# CRSpill.net
KiCad netlist of a schematic drawn in EAGLE
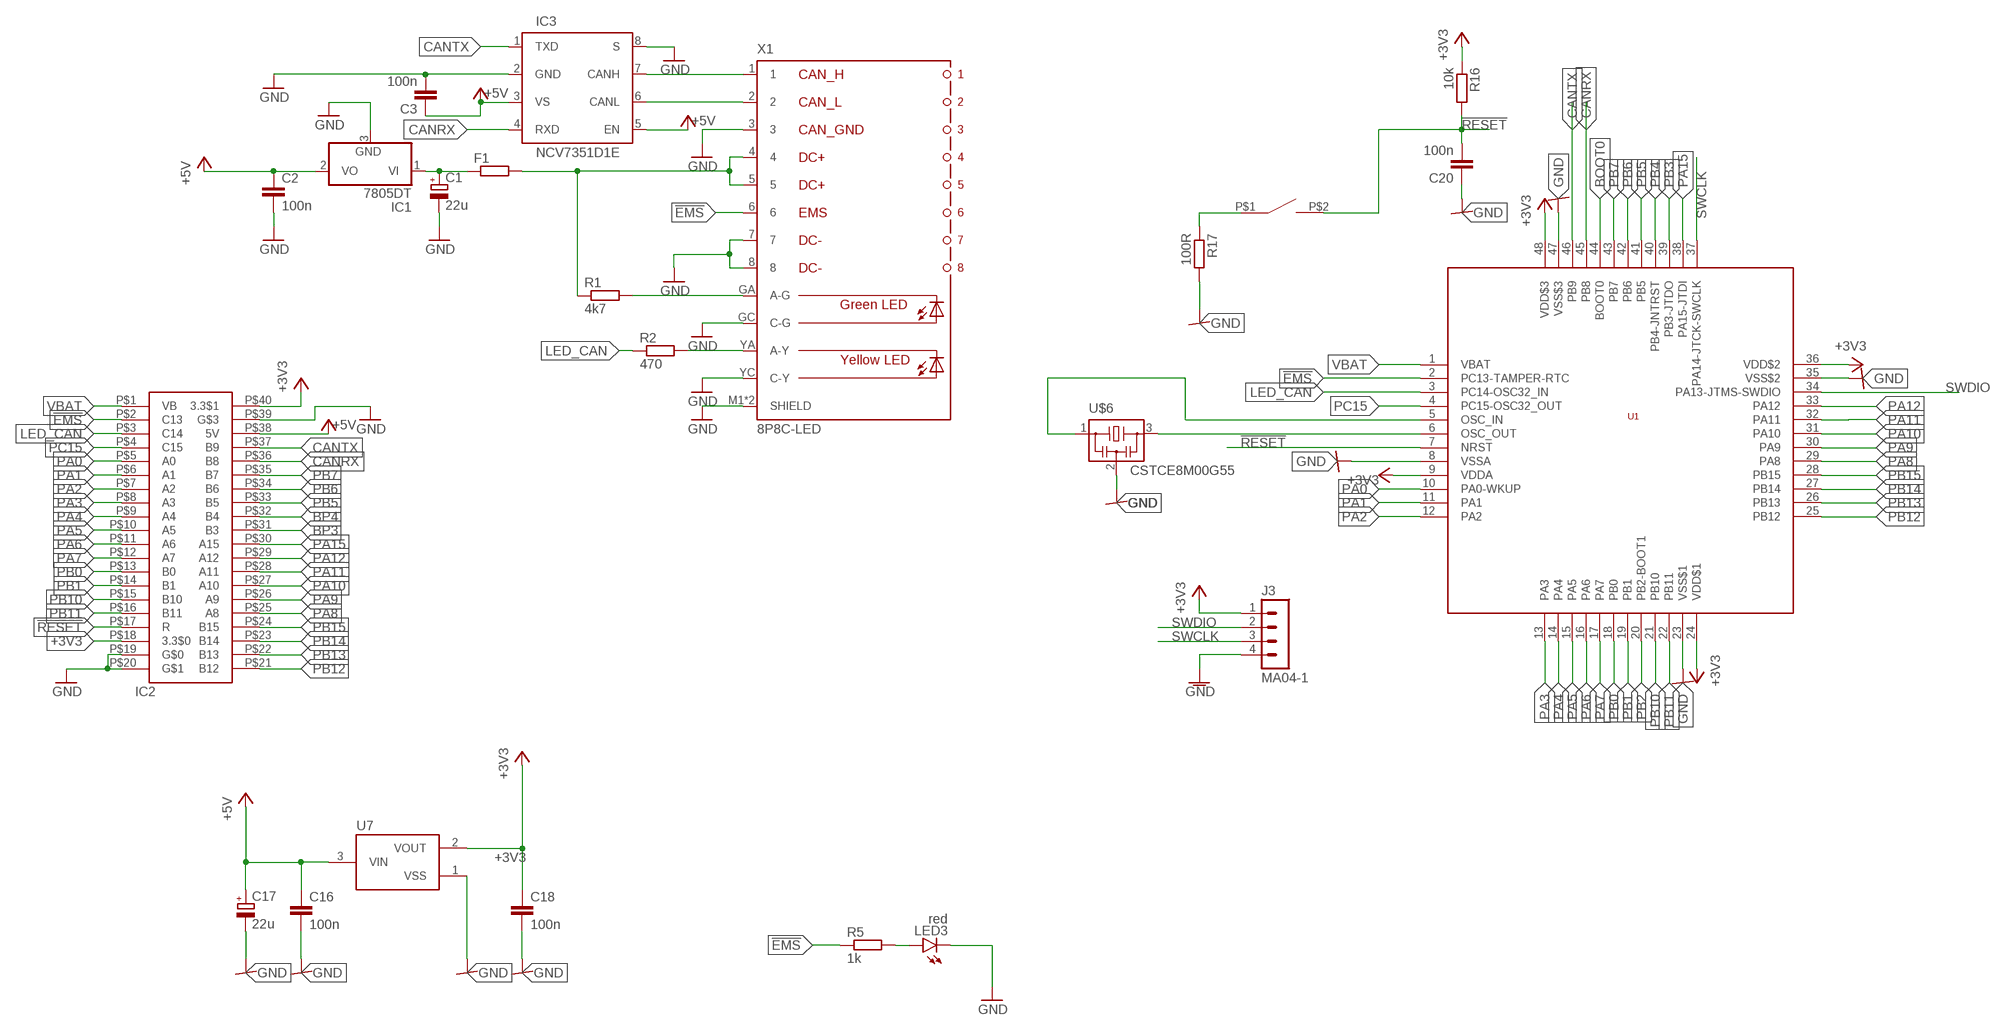
[diagram p0: schematic, sheet 1]

(export (version "E")
  (design (tool "Eeschema 10.0.6"))
  (components
    (comp (ref "C1")
      (value "22u")
      (footprint "eagle-import:E2,5-5")
      (libsource (lib "eagle-import") (part "rcl_334_CPOL-EUE2.5-5"))
    )
    (comp (ref "C2")
      (value "100n")
      (footprint "eagle-import:C0603")
      (libsource (lib "eagle-import") (part "rcl_334_C-EUC0603"))
    )
    (comp (ref "C3")
      (value "100n")
      (footprint "eagle-import:C0603")
      (libsource (lib "eagle-import") (part "rcl_334_C-EUC0603"))
    )
    (comp (ref "C16")
      (value "100n")
      (footprint "eagle-import:C0603")
      (libsource (lib "eagle-import") (part "C-EUC0603"))
    )
    (comp (ref "C17")
      (value "22u")
      (footprint "eagle-import:E2-5")
      (libsource (lib "eagle-import") (part "CPOL-EUE2-5"))
    )
    (comp (ref "C18")
      (value "100n")
      (footprint "eagle-import:C0603")
      (libsource (lib "eagle-import") (part "C-EUC0603"))
    )
    (comp (ref "C20")
      (value "100n")
      (footprint "eagle-import:C0603")
      (libsource (lib "eagle-import") (part "C-EUC0603"))
    )
    (comp (ref "F1")
      (value "R-EU_R1206")
      (footprint "eagle-import:R1206")
      (libsource (lib "eagle-import") (part "rcl_334_R-EU_R1206"))
    )
    (comp (ref "IC1")
      (value "7805DT")
      (footprint "eagle-import:TO252")
      (libsource (lib "eagle-import") (part "78DT05"))
    )
    (comp (ref "IC2")
      (value "BLUE_PILL")
      (footprint "eagle-import:BLUE_PILL")
      (libsource (lib "eagle-import") (part "BLUE_PILL"))
    )
    (comp (ref "IC3")
      (value "NCV7351D1E")
      (footprint "eagle-import:SO08")
      (libsource (lib "eagle-import") (part "NCV7351D1E"))
    )
    (comp (ref "J3")
      (value "MA04-1")
      (footprint "eagle-import:MA04-1")
      (libsource (lib "eagle-import") (part "MA04-1"))
    )
    (comp (ref "LED3")
      (value "red")
      (footprint "eagle-import:CHIPLED_0805")
      (libsource (lib "eagle-import") (part "LEDCHIPLED_0805"))
    )
    (comp (ref "R1")
      (value "4k7")
      (footprint "eagle-import:R0603")
      (libsource (lib "eagle-import") (part "rcl_334_R-EU_R0603"))
    )
    (comp (ref "R2")
      (value "470")
      (footprint "eagle-import:R0603")
      (libsource (lib "eagle-import") (part "rcl_334_R-EU_R0603"))
    )
    (comp (ref "R5")
      (value "1k")
      (footprint "eagle-import:R0603")
      (libsource (lib "eagle-import") (part "rcl_334_R-EU_R0603"))
    )
    (comp (ref "R16")
      (value "10k")
      (footprint "eagle-import:R0603")
      (libsource (lib "eagle-import") (part "R-EU_R0603"))
    )
    (comp (ref "R17")
      (value "100R")
      (footprint "eagle-import:R0603")
      (libsource (lib "eagle-import") (part "R-EU_R0603"))
    )
    (comp (ref "SW1")
      (value "SWITCH_TACTILETOP")
      (footprint "eagle-import:SWITCH_TACTILE_3X6")
      (libsource (lib "eagle-import") (part "SWITCH_TACTILETOP"))
    )
    (comp (ref "U$6")
      (value "CSTCE8M00G55")
      (footprint "eagle-import:CSTCE8M00G55")
      (libsource (lib "eagle-import") (part "CSTCE8M00G55"))
    )
    (comp (ref "U1")
      (value "STM32F103C8")
      (footprint "eagle-import:LQFP48")
      (libsource (lib "eagle-import") (part "STM32F103C8"))
    )
    (comp (ref "U7")
      (value "XC6206")
      (footprint "eagle-import:SOT95P240X110-3")
      (libsource (lib "eagle-import") (part "XC6206"))
    )
    (comp (ref "X1")
      (value "8P8C-LED")
      (footprint "eagle-import:8P8C-LED")
      (libsource (lib "eagle-import") (part "8P8C-LED"))
    )
  )
  (nets
    (net (code "1") (name "+3V3") (class "Default")
      (node (ref "C18") (pin "1") (pinfunction "1_1") (pintype "passive"))
      (node (ref "IC2") (pin "P$18") (pinfunction "3.3$0_P$18") (pintype "passive"))
      (node (ref "IC2") (pin "P$40") (pinfunction "3.3$1_P$40") (pintype "passive"))
      (node (ref "J3") (pin "1") (pinfunction "1_1") (pintype "passive"))
      (node (ref "R16") (pin "1") (pinfunction "1_1") (pintype "passive"))
      (node (ref "U1") (pin "24") (pinfunction "VDD$1_24") (pintype "passive"))
      (node (ref "U1") (pin "36") (pinfunction "VDD$2_36") (pintype "passive"))
      (node (ref "U1") (pin "48") (pinfunction "VDD$3_48") (pintype "passive"))
      (node (ref "U1") (pin "9") (pinfunction "VDDA_9") (pintype "bidirectional"))
      (node (ref "U7") (pin "2") (pinfunction "VOUT_2") (pintype "bidirectional"))
    )
    (net (code "2") (name "+5V") (class "Default")
      (node (ref "C16") (pin "1") (pinfunction "1_1") (pintype "passive"))
      (node (ref "C17") (pin "+") (pinfunction "+_+") (pintype "passive"))
      (node (ref "C2") (pin "1") (pinfunction "1_1") (pintype "passive"))
      (node (ref "C3") (pin "1") (pinfunction "1_1") (pintype "passive"))
      (node (ref "IC1") (pin "2") (pinfunction "VO_2") (pintype "passive"))
      (node (ref "IC2") (pin "P$38") (pinfunction "5V_P$38") (pintype "bidirectional"))
      (node (ref "IC3") (pin "3") (pinfunction "VS_3") (pintype "power_in"))
      (node (ref "IC3") (pin "5") (pinfunction "EN_5") (pintype "input"))
      (node (ref "U7") (pin "3") (pinfunction "VIN_3") (pintype "bidirectional"))
    )
    (net (code "3") (name "/SWCLK") (class "Default")
      (node (ref "J3") (pin "3") (pinfunction "3_3") (pintype "passive"))
      (node (ref "U1") (pin "37") (pinfunction "PA14-JTCK-SWCLK_37") (pintype "bidirectional"))
    )
    (net (code "4") (name "/SWDIO") (class "Default")
      (node (ref "J3") (pin "2") (pinfunction "2_2") (pintype "passive"))
      (node (ref "U1") (pin "34") (pinfunction "PA13-JTMS-SWDIO_34") (pintype "bidirectional"))
    )
    (net (code "5") (name "/~{EMS}") (class "Default")
      (node (ref "IC2") (pin "P$2") (pinfunction "C13_P$2") (pintype "bidirectional"))
      (node (ref "R5") (pin "1") (pinfunction "1_1") (pintype "passive"))
      (node (ref "U1") (pin "2") (pinfunction "PC13-TAMPER-RTC_2") (pintype "bidirectional"))
      (node (ref "X1") (pin "6") (pinfunction "6_6") (pintype "input"))
    )
    (net (code "6") (name "/~{RESET}") (class "Default")
      (node (ref "C20") (pin "2") (pinfunction "2_2") (pintype "passive"))
      (node (ref "IC2") (pin "P$17") (pinfunction "R_P$17") (pintype "bidirectional"))
      (node (ref "R16") (pin "2") (pinfunction "2_2") (pintype "passive"))
      (node (ref "SW1") (pin "P$2") (pinfunction "2_P$2") (pintype "bidirectional"))
      (node (ref "U1") (pin "7") (pinfunction "NRST_7") (pintype "bidirectional"))
    )
    (net (code "7") (name "BOOT0") (class "Default")
      (node (ref "U1") (pin "44") (pinfunction "BOOT0_44") (pintype "input"))
    )
    (net (code "8") (name "BP3") (class "Default")
      (node (ref "IC2") (pin "P$31") (pinfunction "B3_P$31") (pintype "bidirectional"))
    )
    (net (code "9") (name "BP4") (class "Default")
      (node (ref "IC2") (pin "P$32") (pinfunction "B4_P$32") (pintype "bidirectional"))
    )
    (net (code "10") (name "CANRX") (class "Default")
      (node (ref "IC2") (pin "P$36") (pinfunction "B8_P$36") (pintype "bidirectional"))
      (node (ref "IC3") (pin "4") (pinfunction "RXD_4") (pintype "output"))
      (node (ref "U1") (pin "45") (pinfunction "PB8_45") (pintype "bidirectional"))
    )
    (net (code "11") (name "CANTX") (class "Default")
      (node (ref "IC2") (pin "P$37") (pinfunction "B9_P$37") (pintype "bidirectional"))
      (node (ref "IC3") (pin "1") (pinfunction "TXD_1") (pintype "input"))
      (node (ref "U1") (pin "46") (pinfunction "PB9_46") (pintype "bidirectional"))
    )
    (net (code "12") (name "GND") (class "Default")
      (node (ref "C1") (pin "-") (pinfunction "-_-") (pintype "passive"))
      (node (ref "C16") (pin "2") (pinfunction "2_2") (pintype "passive"))
      (node (ref "C17") (pin "-") (pinfunction "-_-") (pintype "passive"))
      (node (ref "C18") (pin "2") (pinfunction "2_2") (pintype "passive"))
      (node (ref "C2") (pin "2") (pinfunction "2_2") (pintype "passive"))
      (node (ref "C20") (pin "1") (pinfunction "1_1") (pintype "passive"))
      (node (ref "C3") (pin "2") (pinfunction "2_2") (pintype "passive"))
      (node (ref "IC1") (pin "3") (pinfunction "GND_3") (pintype "passive"))
      (node (ref "IC2") (pin "P$19") (pinfunction "G$0_P$19") (pintype "passive"))
      (node (ref "IC2") (pin "P$20") (pinfunction "G$1_P$20") (pintype "passive"))
      (node (ref "IC2") (pin "P$39") (pinfunction "G$3_P$39") (pintype "passive"))
      (node (ref "IC3") (pin "2") (pinfunction "GND_2") (pintype "power_in"))
      (node (ref "IC3") (pin "8") (pinfunction "S_8") (pintype "input"))
      (node (ref "J3") (pin "4") (pinfunction "4_4") (pintype "passive"))
      (node (ref "LED3") (pin "C") (pinfunction "C_C") (pintype "passive"))
      (node (ref "R17") (pin "2") (pinfunction "2_2") (pintype "passive"))
      (node (ref "U$6") (pin "2") (pinfunction "2_2") (pintype "passive"))
      (node (ref "U1") (pin "23") (pinfunction "VSS$1_23") (pintype "passive"))
      (node (ref "U1") (pin "35") (pinfunction "VSS$2_35") (pintype "passive"))
      (node (ref "U1") (pin "47") (pinfunction "VSS$3_47") (pintype "passive"))
      (node (ref "U1") (pin "8") (pinfunction "VSSA_8") (pintype "bidirectional"))
      (node (ref "U7") (pin "1") (pinfunction "VSS_1") (pintype "bidirectional"))
      (node (ref "X1") (pin "3") (pinfunction "3_3") (pintype "input"))
      (node (ref "X1") (pin "7") (pinfunction "7_7") (pintype "input"))
      (node (ref "X1") (pin "8") (pinfunction "8_8") (pintype "input"))
      (node (ref "X1") (pin "GC") (pinfunction "C-G_GC") (pintype "passive"))
      (node (ref "X1") (pin "M1") (pinfunction "SHIELD_M1") (pintype "passive"))
      (node (ref "X1") (pin "M2") (pinfunction "SHIELD_M2") (pintype "passive"))
      (node (ref "X1") (pin "YC") (pinfunction "C-Y_YC") (pintype "passive"))
    )
    (net (code "13") (name "LED_CAN") (class "Default")
      (node (ref "IC2") (pin "P$3") (pinfunction "C14_P$3") (pintype "bidirectional"))
      (node (ref "R2") (pin "1") (pinfunction "1_1") (pintype "passive"))
      (node (ref "U1") (pin "3") (pinfunction "PC14-OSC32_IN_3") (pintype "bidirectional"))
    )
    (net (code "14") (name "Net-(F1-Pad2)") (class "Default")
      (node (ref "F1") (pin "2") (pinfunction "2_2") (pintype "passive"))
      (node (ref "R1") (pin "1") (pinfunction "1_1") (pintype "passive"))
      (node (ref "X1") (pin "4") (pinfunction "4_4") (pintype "input"))
      (node (ref "X1") (pin "5") (pinfunction "5_5") (pintype "input"))
    )
    (net (code "15") (name "Net-(IC1-VI)") (class "Default")
      (node (ref "C1") (pin "+") (pinfunction "+_+") (pintype "passive"))
      (node (ref "F1") (pin "1") (pinfunction "1_1") (pintype "passive"))
      (node (ref "IC1") (pin "1") (pinfunction "VI_1") (pintype "input"))
    )
    (net (code "16") (name "Net-(IC3-CANH)") (class "Default")
      (node (ref "IC3") (pin "7") (pinfunction "CANH_7") (pintype "output"))
      (node (ref "X1") (pin "1") (pinfunction "1_1") (pintype "input"))
    )
    (net (code "17") (name "Net-(IC3-CANL)") (class "Default")
      (node (ref "IC3") (pin "6") (pinfunction "CANL_6") (pintype "output"))
      (node (ref "X1") (pin "2") (pinfunction "2_2") (pintype "input"))
    )
    (net (code "18") (name "Net-(LED3-PadA)") (class "Default")
      (node (ref "LED3") (pin "A") (pinfunction "A_A") (pintype "passive"))
      (node (ref "R5") (pin "2") (pinfunction "2_2") (pintype "passive"))
    )
    (net (code "19") (name "Net-(SW1-1)") (class "Default")
      (node (ref "R17") (pin "1") (pinfunction "1_1") (pintype "passive"))
      (node (ref "SW1") (pin "P$1") (pinfunction "1_P$1") (pintype "bidirectional"))
    )
    (net (code "20") (name "Net-(U1-OSC_IN)") (class "Default")
      (node (ref "U$6") (pin "1") (pinfunction "1_1") (pintype "passive"))
      (node (ref "U1") (pin "5") (pinfunction "OSC_IN_5") (pintype "input"))
    )
    (net (code "21") (name "Net-(U1-OSC_OUT)") (class "Default")
      (node (ref "U$6") (pin "3") (pinfunction "3_3") (pintype "passive"))
      (node (ref "U1") (pin "6") (pinfunction "OSC_OUT_6") (pintype "output"))
    )
    (net (code "22") (name "Net-(X1-A-G)") (class "Default")
      (node (ref "R1") (pin "2") (pinfunction "2_2") (pintype "passive"))
      (node (ref "X1") (pin "GA") (pinfunction "A-G_GA") (pintype "passive"))
    )
    (net (code "23") (name "Net-(X1-A-Y)") (class "Default")
      (node (ref "R2") (pin "2") (pinfunction "2_2") (pintype "passive"))
      (node (ref "X1") (pin "YA") (pinfunction "A-Y_YA") (pintype "passive"))
    )
    (net (code "24") (name "PA0") (class "Default")
      (node (ref "IC2") (pin "P$5") (pinfunction "A0_P$5") (pintype "bidirectional"))
      (node (ref "U1") (pin "10") (pinfunction "PA0-WKUP_10") (pintype "bidirectional"))
    )
    (net (code "25") (name "PA1") (class "Default")
      (node (ref "IC2") (pin "P$6") (pinfunction "A1_P$6") (pintype "bidirectional"))
      (node (ref "U1") (pin "11") (pinfunction "PA1_11") (pintype "bidirectional"))
    )
    (net (code "26") (name "PA2") (class "Default")
      (node (ref "IC2") (pin "P$7") (pinfunction "A2_P$7") (pintype "bidirectional"))
      (node (ref "U1") (pin "12") (pinfunction "PA2_12") (pintype "bidirectional"))
    )
    (net (code "27") (name "PA3") (class "Default")
      (node (ref "IC2") (pin "P$8") (pinfunction "A3_P$8") (pintype "bidirectional"))
      (node (ref "U1") (pin "13") (pinfunction "PA3_13") (pintype "bidirectional"))
    )
    (net (code "28") (name "PA4") (class "Default")
      (node (ref "IC2") (pin "P$9") (pinfunction "A4_P$9") (pintype "bidirectional"))
      (node (ref "U1") (pin "14") (pinfunction "PA4_14") (pintype "bidirectional"))
    )
    (net (code "29") (name "PA5") (class "Default")
      (node (ref "IC2") (pin "P$10") (pinfunction "A5_P$10") (pintype "bidirectional"))
      (node (ref "U1") (pin "15") (pinfunction "PA5_15") (pintype "bidirectional"))
    )
    (net (code "30") (name "PA6") (class "Default")
      (node (ref "IC2") (pin "P$11") (pinfunction "A6_P$11") (pintype "bidirectional"))
      (node (ref "U1") (pin "16") (pinfunction "PA6_16") (pintype "bidirectional"))
    )
    (net (code "31") (name "PA7") (class "Default")
      (node (ref "IC2") (pin "P$12") (pinfunction "A7_P$12") (pintype "bidirectional"))
      (node (ref "U1") (pin "17") (pinfunction "PA7_17") (pintype "bidirectional"))
    )
    (net (code "32") (name "PA8") (class "Default")
      (node (ref "IC2") (pin "P$25") (pinfunction "A8_P$25") (pintype "bidirectional"))
      (node (ref "U1") (pin "29") (pinfunction "PA8_29") (pintype "bidirectional"))
    )
    (net (code "33") (name "PA9") (class "Default")
      (node (ref "IC2") (pin "P$26") (pinfunction "A9_P$26") (pintype "bidirectional"))
      (node (ref "U1") (pin "30") (pinfunction "PA9_30") (pintype "bidirectional"))
    )
    (net (code "34") (name "PA10") (class "Default")
      (node (ref "IC2") (pin "P$27") (pinfunction "A10_P$27") (pintype "bidirectional"))
      (node (ref "U1") (pin "31") (pinfunction "PA10_31") (pintype "bidirectional"))
    )
    (net (code "35") (name "PA11") (class "Default")
      (node (ref "IC2") (pin "P$28") (pinfunction "A11_P$28") (pintype "bidirectional"))
      (node (ref "U1") (pin "32") (pinfunction "PA11_32") (pintype "bidirectional"))
    )
    (net (code "36") (name "PA12") (class "Default")
      (node (ref "IC2") (pin "P$29") (pinfunction "A12_P$29") (pintype "bidirectional"))
      (node (ref "U1") (pin "33") (pinfunction "PA12_33") (pintype "bidirectional"))
    )
    (net (code "37") (name "PA15") (class "Default")
      (node (ref "IC2") (pin "P$30") (pinfunction "A15_P$30") (pintype "bidirectional"))
      (node (ref "U1") (pin "38") (pinfunction "PA15-JTDI_38") (pintype "bidirectional"))
    )
    (net (code "38") (name "PB0") (class "Default")
      (node (ref "IC2") (pin "P$13") (pinfunction "B0_P$13") (pintype "bidirectional"))
      (node (ref "U1") (pin "18") (pinfunction "PB0_18") (pintype "bidirectional"))
    )
    (net (code "39") (name "PB1") (class "Default")
      (node (ref "IC2") (pin "P$14") (pinfunction "B1_P$14") (pintype "bidirectional"))
      (node (ref "U1") (pin "19") (pinfunction "PB1_19") (pintype "bidirectional"))
    )
    (net (code "40") (name "PB2") (class "Default")
      (node (ref "U1") (pin "20") (pinfunction "PB2-BOOT1_20") (pintype "bidirectional"))
    )
    (net (code "41") (name "PB3") (class "Default")
      (node (ref "U1") (pin "39") (pinfunction "PB3-JTDO_39") (pintype "bidirectional"))
    )
    (net (code "42") (name "PB4") (class "Default")
      (node (ref "U1") (pin "40") (pinfunction "PB4-JNTRST_40") (pintype "bidirectional"))
    )
    (net (code "43") (name "PB5") (class "Default")
      (node (ref "IC2") (pin "P$33") (pinfunction "B5_P$33") (pintype "bidirectional"))
      (node (ref "U1") (pin "41") (pinfunction "PB5_41") (pintype "bidirectional"))
    )
    (net (code "44") (name "PB6") (class "Default")
      (node (ref "IC2") (pin "P$34") (pinfunction "B6_P$34") (pintype "bidirectional"))
      (node (ref "U1") (pin "42") (pinfunction "PB6_42") (pintype "bidirectional"))
    )
    (net (code "45") (name "PB7") (class "Default")
      (node (ref "IC2") (pin "P$35") (pinfunction "B7_P$35") (pintype "bidirectional"))
      (node (ref "U1") (pin "43") (pinfunction "PB7_43") (pintype "bidirectional"))
    )
    (net (code "46") (name "PB10") (class "Default")
      (node (ref "IC2") (pin "P$15") (pinfunction "B10_P$15") (pintype "bidirectional"))
      (node (ref "U1") (pin "21") (pinfunction "PB10_21") (pintype "bidirectional"))
    )
    (net (code "47") (name "PB11") (class "Default")
      (node (ref "IC2") (pin "P$16") (pinfunction "B11_P$16") (pintype "bidirectional"))
      (node (ref "U1") (pin "22") (pinfunction "PB11_22") (pintype "bidirectional"))
    )
    (net (code "48") (name "PB12") (class "Default")
      (node (ref "IC2") (pin "P$21") (pinfunction "B12_P$21") (pintype "bidirectional"))
      (node (ref "U1") (pin "25") (pinfunction "PB12_25") (pintype "bidirectional"))
    )
    (net (code "49") (name "PB13") (class "Default")
      (node (ref "IC2") (pin "P$22") (pinfunction "B13_P$22") (pintype "bidirectional"))
      (node (ref "U1") (pin "26") (pinfunction "PB13_26") (pintype "bidirectional"))
    )
    (net (code "50") (name "PB14") (class "Default")
      (node (ref "IC2") (pin "P$23") (pinfunction "B14_P$23") (pintype "bidirectional"))
      (node (ref "U1") (pin "27") (pinfunction "PB14_27") (pintype "bidirectional"))
    )
    (net (code "51") (name "PB15") (class "Default")
      (node (ref "IC2") (pin "P$24") (pinfunction "B15_P$24") (pintype "bidirectional"))
      (node (ref "U1") (pin "28") (pinfunction "PB15_28") (pintype "bidirectional"))
    )
    (net (code "52") (name "PC15") (class "Default")
      (node (ref "IC2") (pin "P$4") (pinfunction "C15_P$4") (pintype "bidirectional"))
      (node (ref "U1") (pin "4") (pinfunction "PC15-OSC32_OUT_4") (pintype "bidirectional"))
    )
    (net (code "53") (name "VBAT") (class "Default")
      (node (ref "IC2") (pin "P$1") (pinfunction "VB_P$1") (pintype "bidirectional"))
      (node (ref "U1") (pin "1") (pinfunction "VBAT_1") (pintype "passive"))
    )
  )
)
